# Adafruit_VEML7700.net
KiCad netlist of a schematic drawn in EAGLE
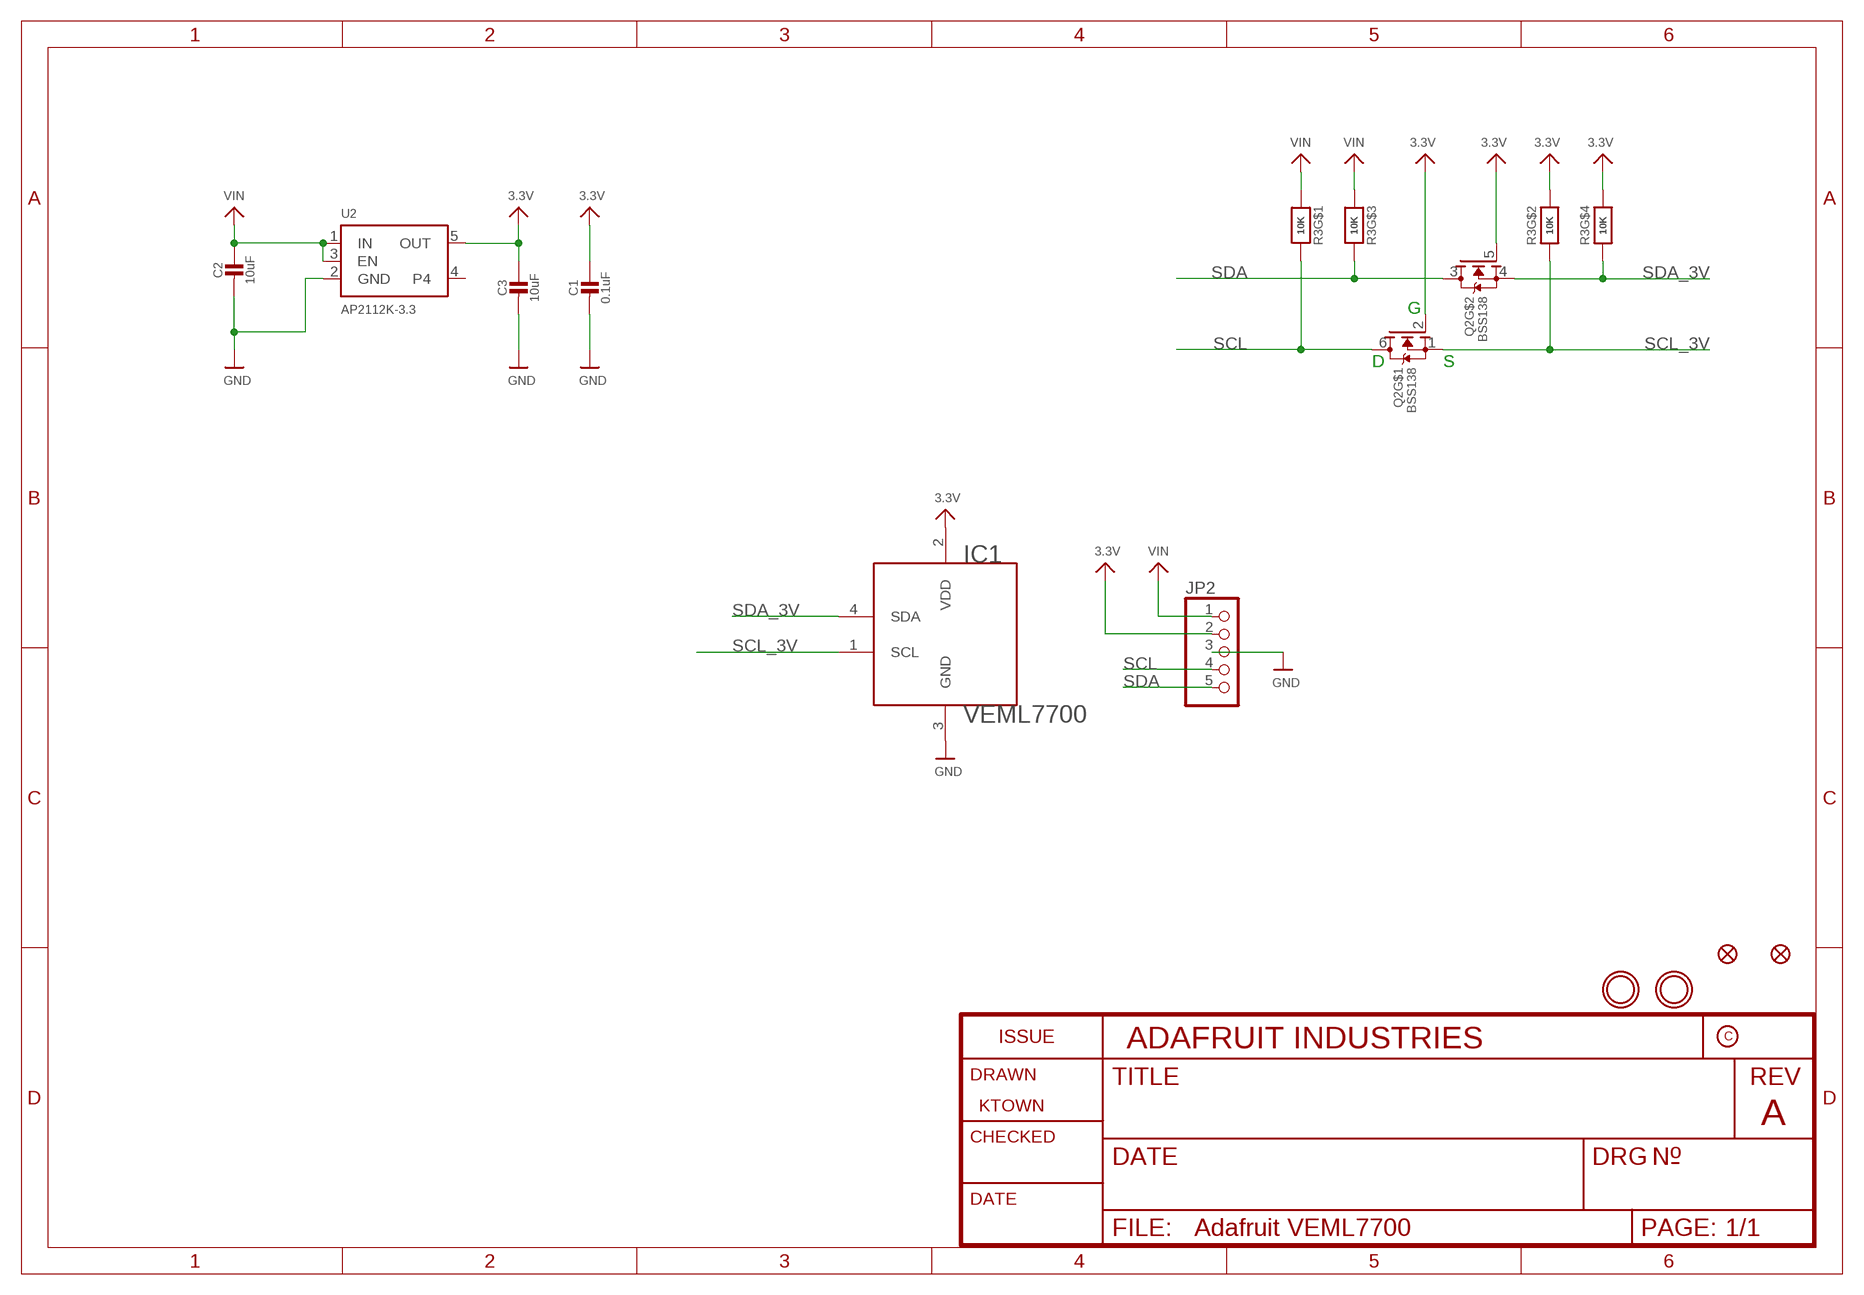
[diagram p0: schematic, sheet 1]

(export (version "E")
  (design (tool "Eeschema 10.0.6"))
  (components
    (comp (ref "C1")
      (value "0.1uF")
      (footprint "eagle-import:0603-NO")
      (libsource (lib "eagle-import") (part "CAP_CERAMIC0603_NO"))
    )
    (comp (ref "C2")
      (value "10uF")
      (footprint "eagle-import:0805-NO")
      (libsource (lib "eagle-import") (part "CAP_CERAMIC0805-NOOUTLINE"))
    )
    (comp (ref "C3")
      (value "10uF")
      (footprint "eagle-import:0805-NO")
      (libsource (lib "eagle-import") (part "CAP_CERAMIC0805-NOOUTLINE"))
    )
    (comp (ref "FID1")
      (value "FIDUCIAL_1MM")
      (footprint "eagle-import:FIDUCIAL_1MM")
      (libsource (lib "eagle-import") (part "FIDUCIAL_1MM"))
    )
    (comp (ref "FID2")
      (value "FIDUCIAL_1MM")
      (footprint "eagle-import:FIDUCIAL_1MM")
      (libsource (lib "eagle-import") (part "FIDUCIAL_1MM"))
    )
    (comp (ref "IC1")
      (value "VEML7700")
      (footprint "eagle-import:VEML7700")
      (libsource (lib "eagle-import") (part "VEML7700"))
    )
    (comp (ref "JP2")
      (value "HEADER-1X5ROUND")
      (footprint "eagle-import:1X05_ROUND")
      (libsource (lib "eagle-import") (part "HEADER-1X5ROUND"))
    )
    (comp (ref "Q2")
      (value "BSS138")
      (footprint "eagle-import:SOT363")
      (libsource (lib "eagle-import") (part "MOSFET-N_DUAL"))
    )
    (comp (ref "R3")
      (value "10K")
      (footprint "eagle-import:RESPACK_4X0603")
      (libsource (lib "eagle-import") (part "RESISTOR_4PACK"))
    )
    (comp (ref "U$3")
      (value "MOUNTINGHOLE2.5")
      (footprint "eagle-import:MOUNTINGHOLE_2.5_PLATED")
      (libsource (lib "eagle-import") (part "MOUNTINGHOLE2.5"))
    )
    (comp (ref "U$4")
      (value "MOUNTINGHOLE2.5")
      (footprint "eagle-import:MOUNTINGHOLE_2.5_PLATED")
      (libsource (lib "eagle-import") (part "MOUNTINGHOLE2.5"))
    )
    (comp (ref "U2")
      (value "AP2112K-3.3")
      (footprint "eagle-import:SOT23-5")
      (libsource (lib "eagle-import") (part "VREG_SOT23-5"))
    )
  )
  (nets
    (net (code "1") (name "/SCL") (class "Default")
      (node (ref "JP2") (pin "4") (pinfunction "4_4") (pintype "passive"))
      (node (ref "Q2") (pin "6") (pinfunction "D_6") (pintype "bidirectional"))
      (node (ref "R3") (pin "8") (pinfunction "2_8") (pintype "passive"))
    )
    (net (code "2") (name "/SCL_3V") (class "Default")
      (node (ref "IC1") (pin "1") (pinfunction "SCL_1") (pintype "bidirectional"))
      (node (ref "Q2") (pin "1") (pinfunction "S_1") (pintype "bidirectional"))
      (node (ref "R3") (pin "7") (pinfunction "2_7") (pintype "passive"))
    )
    (net (code "3") (name "/SDA") (class "Default")
      (node (ref "JP2") (pin "5") (pinfunction "5_5") (pintype "passive"))
      (node (ref "Q2") (pin "3") (pinfunction "D_3") (pintype "bidirectional"))
      (node (ref "R3") (pin "6") (pinfunction "2_6") (pintype "passive"))
    )
    (net (code "4") (name "/SDA_3V") (class "Default")
      (node (ref "IC1") (pin "4") (pinfunction "SDA_4") (pintype "bidirectional"))
      (node (ref "Q2") (pin "4") (pinfunction "S_4") (pintype "bidirectional"))
      (node (ref "R3") (pin "5") (pinfunction "2_5") (pintype "passive"))
    )
    (net (code "5") (name "3.3V") (class "Default")
      (node (ref "C1") (pin "1") (pinfunction "1_1") (pintype "passive"))
      (node (ref "C3") (pin "1") (pinfunction "1_1") (pintype "passive"))
      (node (ref "IC1") (pin "2") (pinfunction "VDD_2") (pintype "power_in"))
      (node (ref "JP2") (pin "2") (pinfunction "2_2") (pintype "passive"))
      (node (ref "Q2") (pin "2") (pinfunction "G_2") (pintype "bidirectional"))
      (node (ref "Q2") (pin "5") (pinfunction "G_5") (pintype "bidirectional"))
      (node (ref "R3") (pin "2") (pinfunction "1_2") (pintype "passive"))
      (node (ref "R3") (pin "4") (pinfunction "1_4") (pintype "passive"))
      (node (ref "U2") (pin "5") (pinfunction "OUT_5") (pintype "power_in"))
    )
    (net (code "6") (name "GND") (class "Default")
      (node (ref "C1") (pin "2") (pinfunction "2_2") (pintype "passive"))
      (node (ref "C2") (pin "2") (pinfunction "2_2") (pintype "passive"))
      (node (ref "C3") (pin "2") (pinfunction "2_2") (pintype "passive"))
      (node (ref "IC1") (pin "3") (pinfunction "GND_3") (pintype "power_in"))
      (node (ref "JP2") (pin "3") (pinfunction "3_3") (pintype "passive"))
      (node (ref "U2") (pin "2") (pinfunction "GND_2") (pintype "power_in"))
    )
    (net (code "7") (name "VIN") (class "Default")
      (node (ref "C2") (pin "1") (pinfunction "1_1") (pintype "passive"))
      (node (ref "JP2") (pin "1") (pinfunction "1_1") (pintype "passive"))
      (node (ref "R3") (pin "1") (pinfunction "1_1") (pintype "passive"))
      (node (ref "R3") (pin "3") (pinfunction "1_3") (pintype "passive"))
      (node (ref "U2") (pin "1") (pinfunction "IN_1") (pintype "power_in"))
      (node (ref "U2") (pin "3") (pinfunction "EN_3") (pintype "input"))
    )
    (net (code "8") (name "unconnected-(U2-P4-Pad4)") (class "Default")
      (node (ref "U2") (pin "4") (pinfunction "P4_4") (pintype "bidirectional"))
    )
  )
)
